# S02-INTERFACES.net
KiCad netlist of a schematic drawn in Altium Designer
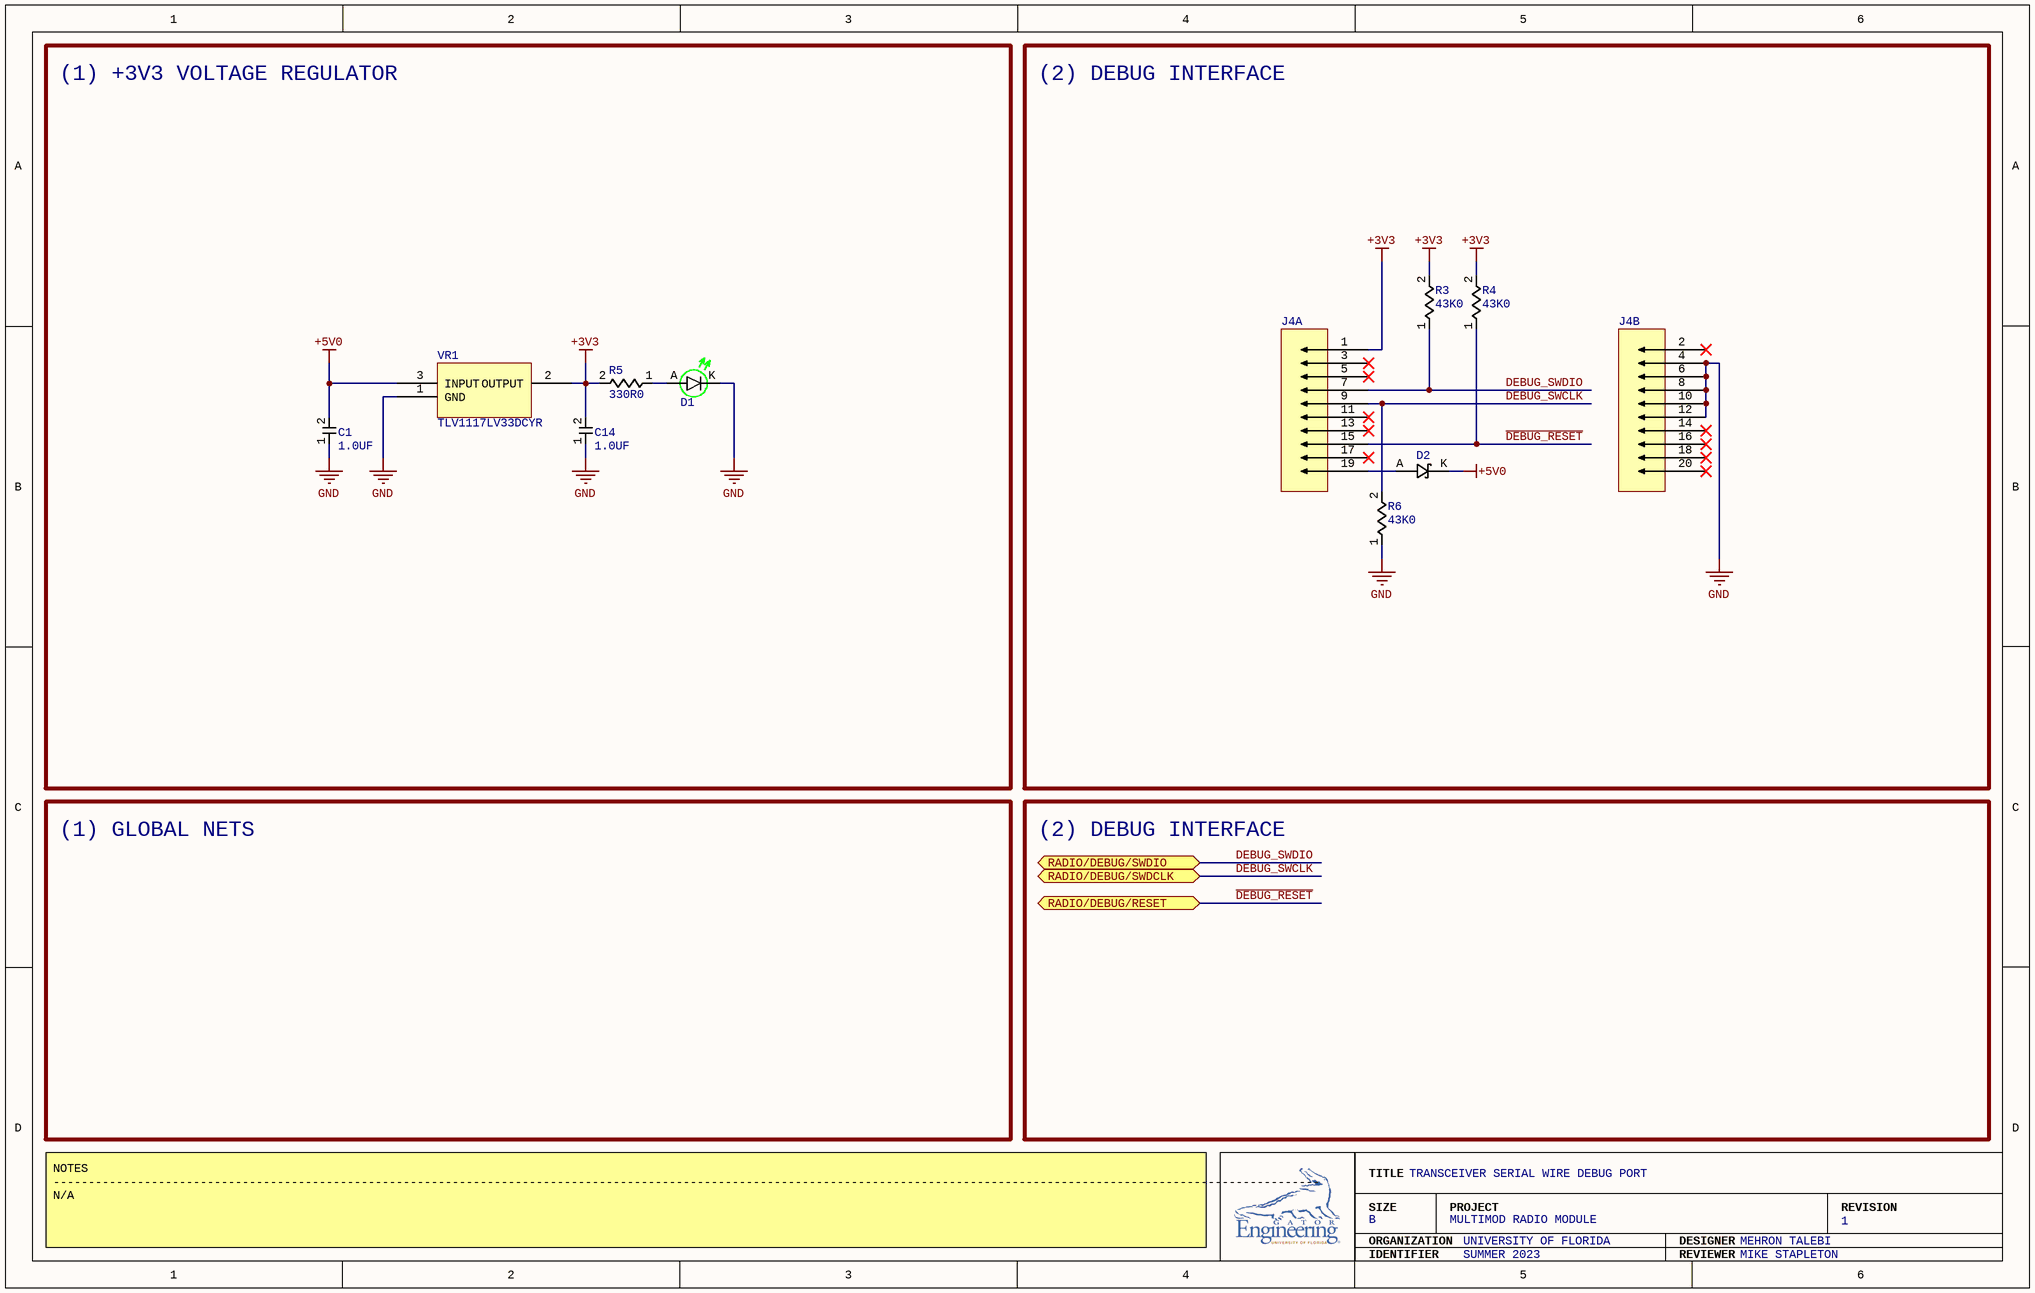
[diagram p0: S02-INTERFACES.SchDoc]

(export (version "E")
  (design (tool "Eeschema 10.0.6"))
  (components
    (comp (ref "C1")
      (value "1.0UF")
      (footprint "CL21B105KAFNFNE")
      (description "CAP CER 1UF 25V X7R 0805")
      (fields (field (name "TOLERANCE") "±10%"))
      (libsource (lib "Master") (part "CL21B105KAFNFNE"))
    )
    (comp (ref "C14")
      (value "1.0UF")
      (footprint "CL21B105KAFNFNE")
      (description "CAP CER 1UF 25V X7R 0805")
      (fields (field (name "TOLERANCE") "±10%"))
      (libsource (lib "Master") (part "CL21B105KAFNFNE"))
    )
    (comp (ref "D1")
      (value "LTST-C171GKT")
      (footprint "LTST-C171GKT")
      (description "LED GREEN CLEAR CHIP SMD")
      (libsource (lib "Master") (part "LTST-C171GKT"))
    )
    (comp (ref "D2")
      (value "RBR5L30BDDTE25")
      (footprint "RBR5L30BDDTE25")
      (description "DIODE SCHOTTKY 30V 5A PMDS")
      (libsource (lib "Master") (part "RBR5L30BDDTE25"))
    )
    (comp (ref "J4")
      (value "3020-20-0300-00")
      (footprint "3020-20-0300-00")
      (description "CONN HEADER SMD 20POS 2.54MM")
      (libsource (lib "Master") (part "3020-20-0300-00"))
    )
    (comp (ref "R3")
      (value "43K0")
      (footprint "RT0805BRD0743KL")
      (description "RES SMD 43K OHM 0.1% 1/8W 0805")
      (fields (field (name "TOLERANCE") "±0.1%"))
      (libsource (lib "Master") (part "RT0805BRD0743KL"))
    )
    (comp (ref "R4")
      (value "43K0")
      (footprint "RT0805BRD0743KL")
      (description "RES SMD 43K OHM 0.1% 1/8W 0805")
      (fields (field (name "TOLERANCE") "±0.1%"))
      (libsource (lib "Master") (part "RT0805BRD0743KL"))
    )
    (comp (ref "R5")
      (value "330R0")
      (footprint "RC0805FR-7W330RL")
      (description "RES 330 OHM 1% 1/4W 0805")
      (fields (field (name "TOLERANCE") "±1%"))
      (libsource (lib "Master") (part "RC0805FR-7W330RL"))
    )
    (comp (ref "R6")
      (value "43K0")
      (footprint "RT0805BRD0743KL")
      (description "RES SMD 43K OHM 0.1% 1/8W 0805")
      (fields (field (name "TOLERANCE") "±0.1%"))
      (libsource (lib "Master") (part "RT0805BRD0743KL"))
    )
    (comp (ref "VR1")
      (value "TLV1117LV33DCYR")
      (footprint "TLV1117LV33DCYR")
      (description "IC REG LINEAR 3.3V 1A SOT223-4")
      (libsource (lib "Master") (part "TLV1117LV33DCYR"))
    )
  )
  (nets
    (net (code "1") (name "+3V3") (class "Default")
      (node (ref "C14") (pin "2") (pinfunction "2_2") (pintype "passive"))
      (node (ref "J4") (pin "1") (pinfunction "1_1") (pintype "passive"))
      (node (ref "R3") (pin "2") (pinfunction "2_2") (pintype "passive"))
      (node (ref "R4") (pin "2") (pinfunction "2_2") (pintype "passive"))
      (node (ref "R5") (pin "2") (pinfunction "2_2") (pintype "passive"))
      (node (ref "VR1") (pin "2") (pinfunction "OUTPUT_2") (pintype "passive"))
    )
    (net (code "2") (name "+5V0") (class "Default")
      (node (ref "C1") (pin "2") (pinfunction "2_2") (pintype "passive"))
      (node (ref "D2") (pin "K") (pinfunction "+_K") (pintype "passive"))
      (node (ref "VR1") (pin "3") (pinfunction "INPUT_3") (pintype "passive"))
    )
    (net (code "3") (name "/DEBUG_RESET") (class "Default")
      (node (ref "J4") (pin "15") (pinfunction "15_15") (pintype "passive"))
      (node (ref "R4") (pin "1") (pinfunction "1_1") (pintype "passive"))
    )
    (net (code "4") (name "/DEBUG_SWCLK") (class "Default")
      (node (ref "J4") (pin "9") (pinfunction "9_9") (pintype "passive"))
      (node (ref "R6") (pin "2") (pinfunction "2_2") (pintype "passive"))
    )
    (net (code "5") (name "/DEBUG_SWDIO") (class "Default")
      (node (ref "J4") (pin "7") (pinfunction "7_7") (pintype "passive"))
      (node (ref "R3") (pin "1") (pinfunction "1_1") (pintype "passive"))
    )
    (net (code "6") (name "GND") (class "Default")
      (node (ref "C1") (pin "1") (pinfunction "1_1") (pintype "passive"))
      (node (ref "C14") (pin "1") (pinfunction "1_1") (pintype "passive"))
      (node (ref "D1") (pin "K") (pinfunction "K_K") (pintype "passive"))
      (node (ref "J4") (pin "10") (pinfunction "10_10") (pintype "passive"))
      (node (ref "J4") (pin "12") (pinfunction "12_12") (pintype "passive"))
      (node (ref "J4") (pin "4") (pinfunction "4_4") (pintype "passive"))
      (node (ref "J4") (pin "6") (pinfunction "6_6") (pintype "passive"))
      (node (ref "J4") (pin "8") (pinfunction "8_8") (pintype "passive"))
      (node (ref "R6") (pin "1") (pinfunction "1_1") (pintype "passive"))
      (node (ref "VR1") (pin "1") (pinfunction "GND_1") (pintype "passive"))
    )
    (net (code "7") (name "Net-(D1-PadA)") (class "Default")
      (node (ref "D1") (pin "A") (pinfunction "A_A") (pintype "passive"))
      (node (ref "R5") (pin "1") (pinfunction "1_1") (pintype "passive"))
    )
    (net (code "8") (name "Net-(D2--)") (class "Default")
      (node (ref "D2") (pin "A") (pinfunction "-_A") (pintype "passive"))
      (node (ref "J4") (pin "19") (pinfunction "19_19") (pintype "passive"))
    )
    (net (code "9") (name "unconnected-(J4-Pad2)") (class "Default")
      (node (ref "J4") (pin "2") (pinfunction "2_2") (pintype "passive+no_connect"))
    )
    (net (code "10") (name "unconnected-(J4-Pad3)") (class "Default")
      (node (ref "J4") (pin "3") (pinfunction "3_3") (pintype "passive+no_connect"))
    )
    (net (code "11") (name "unconnected-(J4-Pad5)") (class "Default")
      (node (ref "J4") (pin "5") (pinfunction "5_5") (pintype "passive+no_connect"))
    )
    (net (code "12") (name "unconnected-(J4-Pad11)") (class "Default")
      (node (ref "J4") (pin "11") (pinfunction "11_11") (pintype "passive+no_connect"))
    )
    (net (code "13") (name "unconnected-(J4-Pad13)") (class "Default")
      (node (ref "J4") (pin "13") (pinfunction "13_13") (pintype "passive+no_connect"))
    )
    (net (code "14") (name "unconnected-(J4-Pad14)") (class "Default")
      (node (ref "J4") (pin "14") (pinfunction "14_14") (pintype "passive+no_connect"))
    )
    (net (code "15") (name "unconnected-(J4-Pad16)") (class "Default")
      (node (ref "J4") (pin "16") (pinfunction "16_16") (pintype "passive+no_connect"))
    )
    (net (code "16") (name "unconnected-(J4-Pad17)") (class "Default")
      (node (ref "J4") (pin "17") (pinfunction "17_17") (pintype "passive+no_connect"))
    )
    (net (code "17") (name "unconnected-(J4-Pad18)") (class "Default")
      (node (ref "J4") (pin "18") (pinfunction "18_18") (pintype "passive+no_connect"))
    )
    (net (code "18") (name "unconnected-(J4-Pad20)") (class "Default")
      (node (ref "J4") (pin "20") (pinfunction "20_20") (pintype "passive+no_connect"))
    )
  )
)
